# RS485.net
KiCad netlist of a schematic drawn in Altium Designer
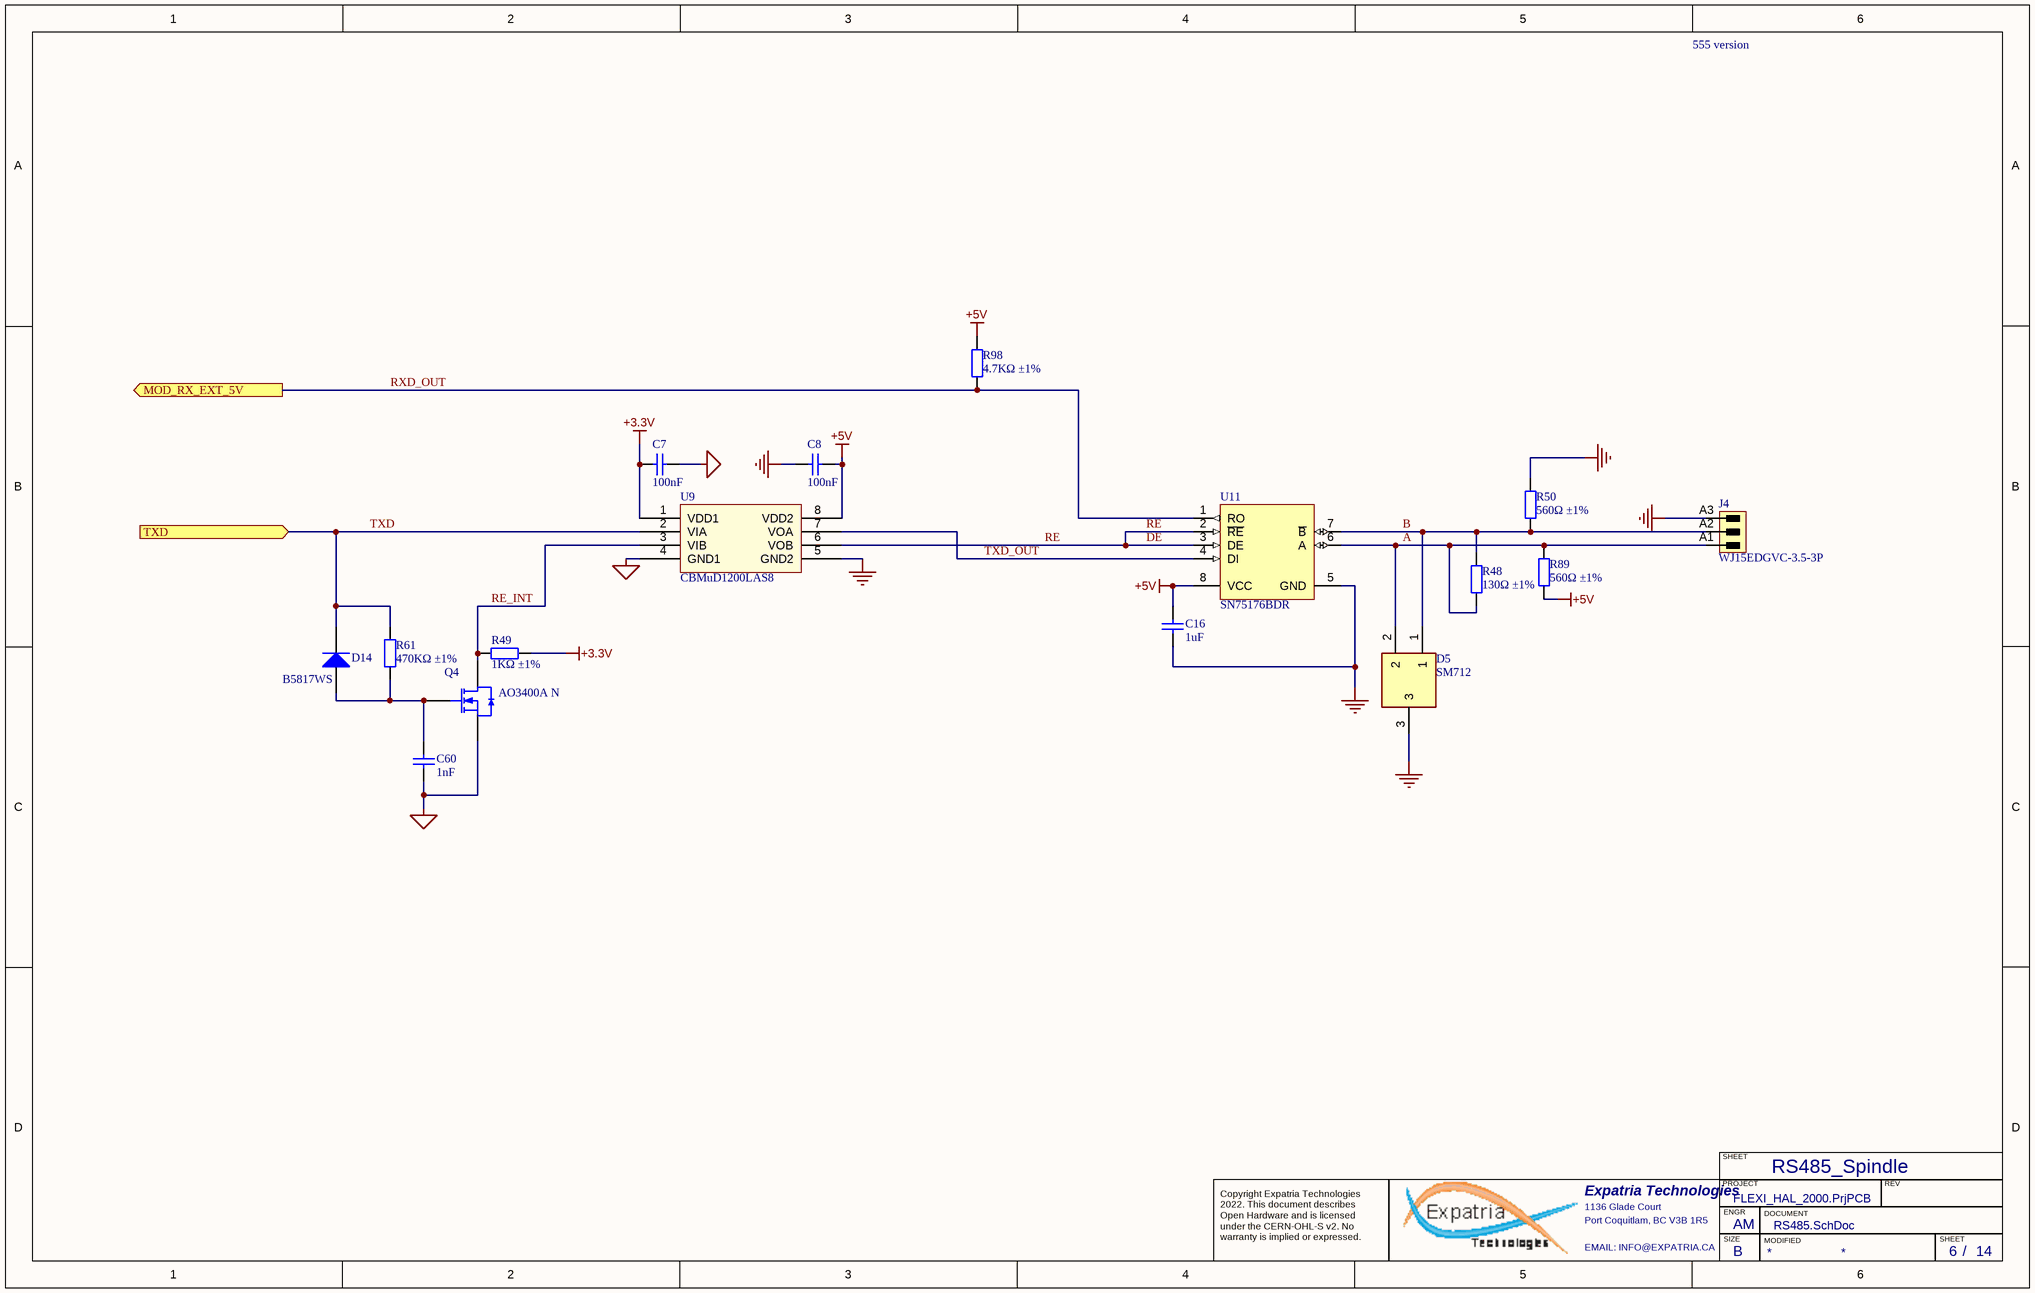
[diagram p0: RS485.SchDoc]

(export (version "E")
  (design (tool "Eeschema 10.0.6"))
  (components
    (comp (ref "C7")
      (value "100nF")
      (footprint "0603_C")
      (description "Chip capacitors")
      (fields (field (name "MANUFACTURER") "YAGEO") (field (name "PARTNUMBER") "CC0603KRX7R9BB104"))
      (libsource (lib "Cap") (part "0603 100nF (104) 10% 50V"))
    )
    (comp (ref "C8")
      (value "100nF")
      (footprint "0603_C")
      (description "Chip capacitors")
      (fields (field (name "MANUFACTURER") "YAGEO") (field (name "PARTNUMBER") "CC0603KRX7R9BB104"))
      (libsource (lib "Cap") (part "0603 100nF (104) 10% 50V"))
    )
    (comp (ref "C16")
      (value "1uF")
      (footprint "0603_C")
      (description "Chip capacitors")
      (fields
        (field (name "MANUFACTURER") "Samsung Electro-Mechanics")
        (field (name "PARTNUMBER") "CL10A105KB8NNNC")
      )
      (libsource (lib "Cap") (part "0603 1uF (105) 10% 50V"))
    )
    (comp (ref "C60")
      (value "1nF")
      (footprint "0603_C")
      (description "Chip capacitors")
      (fields
        (field (name "MANUFACTURER") "Samsung Electro-Mechanics")
        (field (name "PARTNUMBER") "CL10B102KB8NNNC")
      )
      (libsource (lib "Cap") (part "0603 1nF (102) 10% 50V"))
    )
    (comp (ref "D5")
      (value "SM712")
      (footprint "SamacSys:SOT95P230X117-3N")
      (description "Bidirectional 12V (Max), 7V (Max) 7.5V / 13.3V 10V / 20V 12A(8/20us) SOT-23-3 TVS RoHS")
      (libsource (lib "*") (part "CDSOT23-SM712"))
    )
    (comp (ref "D14")
      (value "B5817WS")
      (footprint "SOD-323")
      (description "20V 750mV@3A 1A SOD-323 Schottky Barrier Diodes (SBD) ROHS")
      (libsource (lib "Diode") (part "SOD-123 B5819W  SL"))
    )
    (comp (ref "J4")
      (value "WJ15EDGVC-3.5-3P")
      (footprint "691321100003 - 3.5mm  3p")
      (fields (field (name "MANUFACTURER") "Ningbo Kangnex Elec"))
      (libsource (lib "Universal_CNC_Breakout") (part "3.5mm Terminal Header 3p"))
    )
    (comp (ref "Q4")
      (value "AO3400A N")
      (footprint "SOT-23-3L")
      (description "MOS(场效应管)")
      (libsource (lib "MOS") (part "AO3400A N道沟 X0YV1T SOT-23"))
    )
    (comp (ref "R48")
      (value "130Ω ±1%")
      (footprint "0603_R")
      (description "Chip resistor")
      (fields (field (name "MANUFACTURER") "Uniroyal Elec") (field (name "PARTNUMBER") "0603WAF1300T5E"))
      (libsource (lib "RES") (part "0603 130R (1300) 1%"))
    )
    (comp (ref "R49")
      (value "1KΩ ±1%")
      (footprint "0603_R")
      (description "Chip resistor")
      (fields (field (name "MANUFACTURER") "Uniroyal Elec") (field (name "PARTNUMBER") "0603WAF1001T5E"))
      (libsource (lib "RES") (part "0603 1K (1001) 1%"))
    )
    (comp (ref "R50")
      (value "560Ω ±1%")
      (footprint "0603_R")
      (description "Chip resistor")
      (fields (field (name "MANUFACTURER") "Uniroyal Elec") (field (name "PARTNUMBER") "0603WAF5600T5E"))
      (libsource (lib "RES") (part "0603 560R (5600) 1%"))
    )
    (comp (ref "R61")
      (value "470KΩ ±1%")
      (footprint "0603_R")
      (description "Chip resistor")
      (fields (field (name "MANUFACTURER") "Uniroyal Elec") (field (name "PARTNUMBER") "0603WAF4703T5E"))
      (libsource (lib "RES") (part "0603 470K (4703) 1%"))
    )
    (comp (ref "R89")
      (value "560Ω ±1%")
      (footprint "0603_R")
      (description "Chip resistor")
      (fields (field (name "MANUFACTURER") "Uniroyal Elec") (field (name "PARTNUMBER") "0603WAF5600T5E"))
      (libsource (lib "RES") (part "0603 560R (5600) 1%"))
    )
    (comp (ref "R98")
      (value "4.7KΩ ±1%")
      (footprint "0603_R")
      (description "Chip resistor")
      (fields (field (name "MANUFACTURER") "Uniroyal Elec") (field (name "PARTNUMBER") "0603WAF4701T5E"))
      (libsource (lib "RES") (part "0603 4.7K (4701) 1%"))
    )
    (comp (ref "U9")
      (value "CBMuD1200LAS8")
      (footprint "SOIC-8_150mil")
      (description "Dual Channel Isolator")
      (libsource (lib "IC") (part "CBMuD1200LAS8"))
    )
    (comp (ref "U11")
      (value "SN75176BDR")
      (footprint "SOIC-8_150mil")
      (description "RS-485/RS-422")
      (libsource (lib "IC") (part "SN75176BDR_[C7063]"))
    )
  )
  (nets
    (net (code "1") (name "+3.3V") (class "Default")
      (node (ref "C7") (pin "1") (pinfunction "1_1") (pintype "passive"))
      (node (ref "R49") (pin "1") (pinfunction "1_1") (pintype "passive"))
      (node (ref "U9") (pin "1") (pinfunction "VDD1_1") (pintype "passive"))
    )
    (net (code "2") (name "+5V") (class "Default")
      (node (ref "C16") (pin "2") (pinfunction "2_2") (pintype "passive"))
      (node (ref "C8") (pin "2") (pinfunction "2_2") (pintype "passive"))
      (node (ref "R89") (pin "2") (pinfunction "2_2") (pintype "passive"))
      (node (ref "R98") (pin "2") (pinfunction "2_2") (pintype "passive"))
      (node (ref "U11") (pin "8") (pinfunction "VCC_8") (pintype "power_in"))
      (node (ref "U9") (pin "8") (pinfunction "VDD2_8") (pintype "passive"))
    )
    (net (code "3") (name "/A") (class "Default")
      (node (ref "D5") (pin "2") (pinfunction "2_2") (pintype "passive"))
      (node (ref "J4") (pin "A1") (pinfunction "A1_A1") (pintype "passive"))
      (node (ref "R48") (pin "1") (pinfunction "1_1") (pintype "passive"))
      (node (ref "R89") (pin "1") (pinfunction "1_1") (pintype "passive"))
      (node (ref "U11") (pin "6") (pinfunction "A_6") (pintype "bidirectional"))
    )
    (net (code "4") (name "/B") (class "Default")
      (node (ref "D5") (pin "1") (pinfunction "1_1") (pintype "passive"))
      (node (ref "J4") (pin "A2") (pinfunction "A2_A2") (pintype "passive"))
      (node (ref "R48") (pin "2") (pinfunction "2_2") (pintype "passive"))
      (node (ref "R50") (pin "2") (pinfunction "2_2") (pintype "passive"))
      (node (ref "U11") (pin "7") (pinfunction "~{B}_7") (pintype "bidirectional"))
    )
    (net (code "5") (name "/DE") (class "Default")
      (node (ref "U11") (pin "2") (pinfunction "~{RE}_2") (pintype "input"))
      (node (ref "U11") (pin "3") (pinfunction "DE_3") (pintype "input"))
      (node (ref "U9") (pin "6") (pinfunction "VOB_6") (pintype "passive"))
    )
    (net (code "6") (name "/RE_INT") (class "Default")
      (node (ref "Q4") (pin "3") (pinfunction "D_3") (pintype "passive"))
      (node (ref "R49") (pin "2") (pinfunction "2_2") (pintype "passive"))
      (node (ref "U9") (pin "3") (pinfunction "VIB_3") (pintype "passive"))
    )
    (net (code "7") (name "/RXD_OUT") (class "Default")
      (node (ref "R98") (pin "1") (pinfunction "1_1") (pintype "passive"))
      (node (ref "U11") (pin "1") (pinfunction "RO_1") (pintype "output"))
    )
    (net (code "8") (name "/TXD") (class "Default")
      (node (ref "D14") (pin "2") (pinfunction "K_2") (pintype "passive"))
      (node (ref "R61") (pin "1") (pinfunction "1_1") (pintype "passive"))
      (node (ref "U9") (pin "2") (pinfunction "VIA_2") (pintype "passive"))
    )
    (net (code "9") (name "/TXD_OUT") (class "Default")
      (node (ref "U11") (pin "4") (pinfunction "DI_4") (pintype "input"))
      (node (ref "U9") (pin "7") (pinfunction "VOA_7") (pintype "passive"))
    )
    (net (code "10") (name "GND") (class "Default")
      (node (ref "C16") (pin "1") (pinfunction "1_1") (pintype "passive"))
      (node (ref "C8") (pin "1") (pinfunction "1_1") (pintype "passive"))
      (node (ref "D5") (pin "3") (pinfunction "3_3") (pintype "passive"))
      (node (ref "J4") (pin "A3") (pinfunction "A3_A3") (pintype "passive"))
      (node (ref "R50") (pin "1") (pinfunction "1_1") (pintype "passive"))
      (node (ref "U11") (pin "5") (pinfunction "GND_5") (pintype "power_in"))
      (node (ref "U9") (pin "5") (pinfunction "GND2_5") (pintype "passive"))
    )
    (net (code "11") (name "MCU_GND") (class "Default")
      (node (ref "C60") (pin "2") (pinfunction "2_2") (pintype "passive"))
      (node (ref "C7") (pin "2") (pinfunction "2_2") (pintype "passive"))
      (node (ref "Q4") (pin "2") (pinfunction "S_2") (pintype "passive"))
      (node (ref "U9") (pin "4") (pinfunction "GND1_4") (pintype "passive"))
    )
    (net (code "12") (name "Net-(D14-A)") (class "Default")
      (node (ref "C60") (pin "1") (pinfunction "1_1") (pintype "passive"))
      (node (ref "D14") (pin "1") (pinfunction "A_1") (pintype "passive"))
      (node (ref "Q4") (pin "1") (pinfunction "G_1") (pintype "passive"))
      (node (ref "R61") (pin "2") (pinfunction "2_2") (pintype "passive"))
    )
  )
)
